# hat2.net
KiCad netlist of a schematic drawn in EAGLE
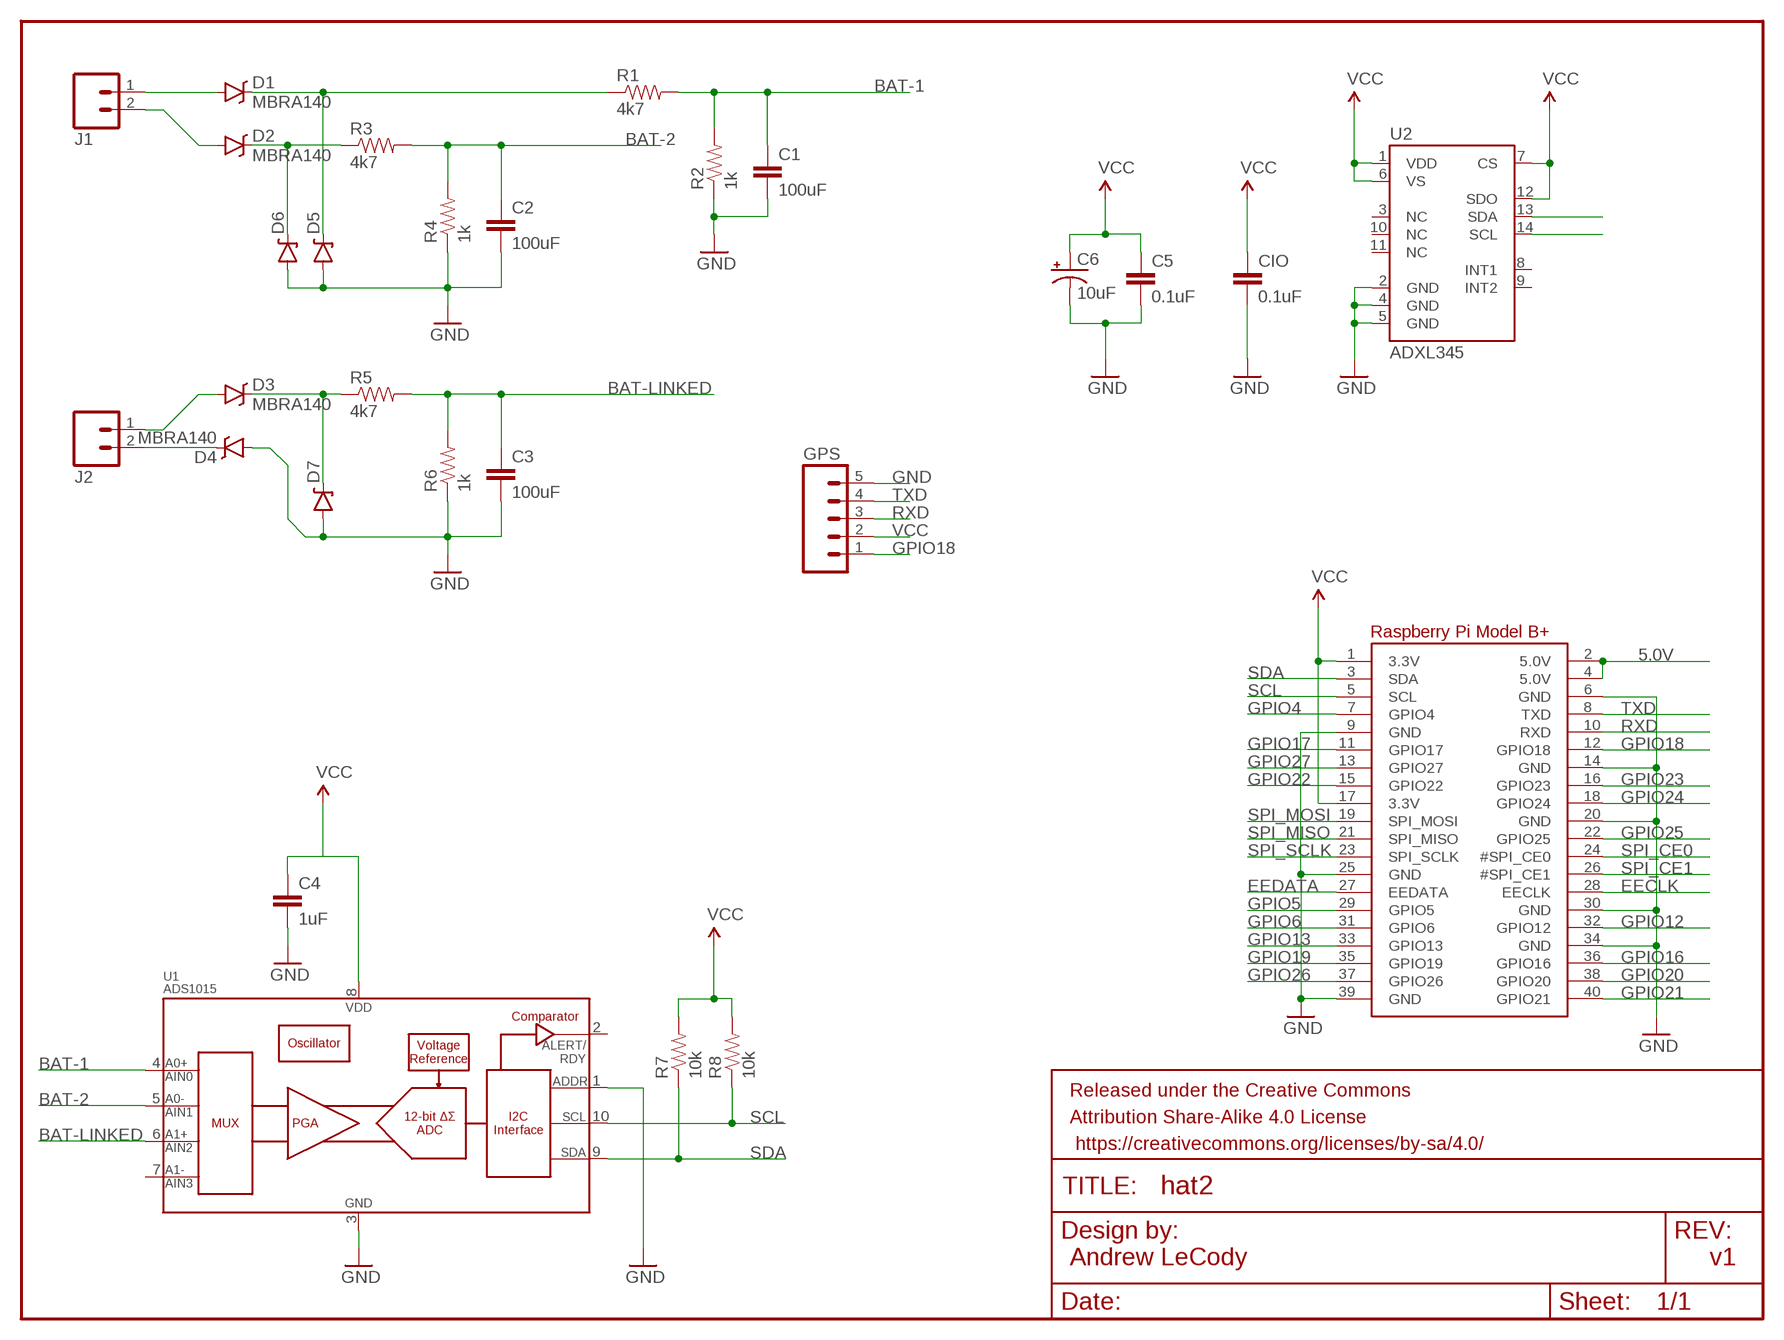
[diagram p0: schematic, sheet 1]

(export (version "E")
  (design (tool "Eeschema 10.0.6"))
  (components
    (comp (ref "C1")
      (value "100uF")
      (footprint "eagle-import:0603-CAP")
      (libsource (lib "eagle-import") (part "SparkFun-Passives_CAP0603-CAP"))
    )
    (comp (ref "C2")
      (value "100uF")
      (footprint "eagle-import:0603-CAP")
      (libsource (lib "eagle-import") (part "SparkFun-Passives_CAP0603-CAP"))
    )
    (comp (ref "C3")
      (value "100uF")
      (footprint "eagle-import:0603-CAP")
      (libsource (lib "eagle-import") (part "SparkFun-Passives_CAP0603-CAP"))
    )
    (comp (ref "C4")
      (value "1uF")
      (footprint "eagle-import:0603-CAP")
      (libsource (lib "eagle-import") (part "SparkFun-Passives_CAP0603-CAP"))
    )
    (comp (ref "C5")
      (value "0.1uF")
      (footprint "eagle-import:0603-CAP")
      (libsource (lib "eagle-import") (part "CAP0603-CAP"))
    )
    (comp (ref "C6")
      (value "10uF")
      (footprint "eagle-import:EIA3216")
      (libsource (lib "eagle-import") (part "CAP_POL1206"))
    )
    (comp (ref "CIO")
      (value "0.1uF")
      (footprint "eagle-import:0603-CAP")
      (libsource (lib "eagle-import") (part "CAP0603-CAP"))
    )
    (comp (ref "D1")
      (value "MBRA140")
      (footprint "eagle-import:SMA-DIODE")
      (libsource (lib "eagle-import") (part "DIODE-SCHOTTKY-MBRA140"))
    )
    (comp (ref "D2")
      (value "MBRA140")
      (footprint "eagle-import:SMA-DIODE")
      (libsource (lib "eagle-import") (part "DIODE-SCHOTTKY-MBRA140"))
    )
    (comp (ref "D3")
      (value "MBRA140")
      (footprint "eagle-import:SMA-DIODE")
      (libsource (lib "eagle-import") (part "DIODE-SCHOTTKY-MBRA140"))
    )
    (comp (ref "D4")
      (value "MBRA140")
      (footprint "eagle-import:SMA-DIODE")
      (libsource (lib "eagle-import") (part "DIODE-SCHOTTKY-MBRA140"))
    )
    (comp (ref "D5")
      (value "DIODE-ZENERSMB")
      (footprint "eagle-import:SMB-DIODE")
      (libsource (lib "eagle-import") (part "DIODE-ZENERSMB"))
    )
    (comp (ref "D6")
      (value "DIODE-ZENERSMB")
      (footprint "eagle-import:SMB-DIODE")
      (libsource (lib "eagle-import") (part "DIODE-ZENERSMB"))
    )
    (comp (ref "D7")
      (value "DIODE-ZENERSMB")
      (footprint "eagle-import:SMB-DIODE")
      (libsource (lib "eagle-import") (part "DIODE-ZENERSMB"))
    )
    (comp (ref "FRAME1")
      (value "FRAME-LETTER")
      (footprint "eagle-import:CREATIVE_COMMONS")
      (libsource (lib "eagle-import") (part "FRAME-LETTER"))
    )
    (comp (ref "GPS")
      (value "M05PTH")
      (footprint "eagle-import:1X05")
      (libsource (lib "eagle-import") (part "M05PTH"))
    )
    (comp (ref "J1")
      (value "M025MM")
      (footprint "eagle-import:SCREWTERMINAL-5MM-2")
      (libsource (lib "eagle-import") (part "M025MM"))
    )
    (comp (ref "J2")
      (value "M025MM")
      (footprint "eagle-import:SCREWTERMINAL-5MM-2")
      (libsource (lib "eagle-import") (part "M025MM"))
    )
    (comp (ref "R1")
      (value "4k7")
      (footprint "eagle-import:0603-RES")
      (libsource (lib "eagle-import") (part "RESISTOR0603-RES"))
    )
    (comp (ref "R2")
      (value "1k")
      (footprint "eagle-import:0603-RES")
      (libsource (lib "eagle-import") (part "RESISTOR0603-RES"))
    )
    (comp (ref "R3")
      (value "4k7")
      (footprint "eagle-import:0603-RES")
      (libsource (lib "eagle-import") (part "RESISTOR0603-RES"))
    )
    (comp (ref "R4")
      (value "1k")
      (footprint "eagle-import:0603-RES")
      (libsource (lib "eagle-import") (part "RESISTOR0603-RES"))
    )
    (comp (ref "R5")
      (value "4k7")
      (footprint "eagle-import:0603-RES")
      (libsource (lib "eagle-import") (part "RESISTOR0603-RES"))
    )
    (comp (ref "R6")
      (value "1k")
      (footprint "eagle-import:0603-RES")
      (libsource (lib "eagle-import") (part "RESISTOR0603-RES"))
    )
    (comp (ref "R7")
      (value "10k")
      (footprint "eagle-import:0603-RES")
      (libsource (lib "eagle-import") (part "RESISTOR0603-RES"))
    )
    (comp (ref "R8")
      (value "10k")
      (footprint "eagle-import:0603-RES")
      (libsource (lib "eagle-import") (part "RESISTOR0603-RES"))
    )
    (comp (ref "RPI1")
      (value "RASPBERRYPI_BPLUS_HATNOSLOTS")
      (footprint "eagle-import:PI_HAT_NOSLOTS")
      (libsource (lib "eagle-import") (part "RASPBERRYPI_BPLUS_HATNOSLOTS"))
    )
    (comp (ref "U1")
      (value "ADS1015")
      (footprint "eagle-import:MSOP10")
      (libsource (lib "eagle-import") (part "ADS1015"))
    )
    (comp (ref "U2")
      (value "ADXL345")
      (footprint "eagle-import:LGA14")
      (libsource (lib "eagle-import") (part "ADXL345"))
    )
  )
  (nets
    (net (code "1") (name "/5.0V") (class "Default")
      (node (ref "RPI1") (pin "2") (pinfunction "5.0V_2") (pintype "power_in"))
      (node (ref "RPI1") (pin "4") (pinfunction "5.0V_4") (pintype "power_in"))
    )
    (net (code "2") (name "/BAT-1") (class "Default")
      (node (ref "C1") (pin "1") (pinfunction "1_1") (pintype "passive"))
      (node (ref "R1") (pin "2") (pinfunction "2_2") (pintype "passive"))
      (node (ref "R2") (pin "2") (pinfunction "2_2") (pintype "passive"))
      (node (ref "U1") (pin "4") (pinfunction "AIN0_4") (pintype "bidirectional"))
    )
    (net (code "3") (name "/BAT-2") (class "Default")
      (node (ref "C2") (pin "1") (pinfunction "1_1") (pintype "passive"))
      (node (ref "R3") (pin "2") (pinfunction "2_2") (pintype "passive"))
      (node (ref "R4") (pin "2") (pinfunction "2_2") (pintype "passive"))
      (node (ref "U1") (pin "5") (pinfunction "AIN1_5") (pintype "bidirectional"))
    )
    (net (code "4") (name "/BAT-LINKED") (class "Default")
      (node (ref "C3") (pin "1") (pinfunction "1_1") (pintype "passive"))
      (node (ref "R5") (pin "2") (pinfunction "2_2") (pintype "passive"))
      (node (ref "R6") (pin "2") (pinfunction "2_2") (pintype "passive"))
      (node (ref "U1") (pin "6") (pinfunction "AIN2_6") (pintype "bidirectional"))
    )
    (net (code "5") (name "/EECLK") (class "Default")
      (node (ref "RPI1") (pin "28") (pinfunction "EECLK_28") (pintype "power_in"))
    )
    (net (code "6") (name "/EEDATA") (class "Default")
      (node (ref "RPI1") (pin "27") (pinfunction "EEDATA_27") (pintype "bidirectional"))
    )
    (net (code "7") (name "/GPIO4") (class "Default")
      (node (ref "RPI1") (pin "7") (pinfunction "GPIO4_7") (pintype "bidirectional"))
    )
    (net (code "8") (name "/GPIO5") (class "Default")
      (node (ref "RPI1") (pin "29") (pinfunction "GPIO5_29") (pintype "bidirectional"))
    )
    (net (code "9") (name "/GPIO6") (class "Default")
      (node (ref "RPI1") (pin "31") (pinfunction "GPIO6_31") (pintype "power_in"))
    )
    (net (code "10") (name "/GPIO12") (class "Default")
      (node (ref "RPI1") (pin "32") (pinfunction "GPIO12_32") (pintype "bidirectional"))
    )
    (net (code "11") (name "/GPIO13") (class "Default")
      (node (ref "RPI1") (pin "33") (pinfunction "GPIO13_33") (pintype "bidirectional"))
    )
    (net (code "12") (name "/GPIO16") (class "Default")
      (node (ref "RPI1") (pin "36") (pinfunction "GPIO16_36") (pintype "power_in"))
    )
    (net (code "13") (name "/GPIO17") (class "Default")
      (node (ref "RPI1") (pin "11") (pinfunction "GPIO17_11") (pintype "bidirectional"))
    )
    (net (code "14") (name "/GPIO18") (class "Default")
      (node (ref "GPS") (pin "1") (pinfunction "1_1") (pintype "passive"))
      (node (ref "RPI1") (pin "12") (pinfunction "GPIO18_12") (pintype "bidirectional"))
    )
    (net (code "15") (name "/GPIO19") (class "Default")
      (node (ref "RPI1") (pin "35") (pinfunction "GPIO19_35") (pintype "bidirectional"))
    )
    (net (code "16") (name "/GPIO20") (class "Default")
      (node (ref "RPI1") (pin "38") (pinfunction "GPIO20_38") (pintype "bidirectional"))
    )
    (net (code "17") (name "/GPIO21") (class "Default")
      (node (ref "RPI1") (pin "40") (pinfunction "GPIO21_40") (pintype "bidirectional"))
    )
    (net (code "18") (name "/GPIO22") (class "Default")
      (node (ref "RPI1") (pin "15") (pinfunction "GPIO22_15") (pintype "bidirectional"))
    )
    (net (code "19") (name "/GPIO23") (class "Default")
      (node (ref "RPI1") (pin "16") (pinfunction "GPIO23_16") (pintype "bidirectional"))
    )
    (net (code "20") (name "/GPIO24") (class "Default")
      (node (ref "RPI1") (pin "18") (pinfunction "GPIO24_18") (pintype "bidirectional"))
    )
    (net (code "21") (name "/GPIO25") (class "Default")
      (node (ref "RPI1") (pin "22") (pinfunction "GPIO25_22") (pintype "bidirectional"))
    )
    (net (code "22") (name "/GPIO26") (class "Default")
      (node (ref "RPI1") (pin "37") (pinfunction "GPIO26_37") (pintype "bidirectional"))
    )
    (net (code "23") (name "/GPIO27") (class "Default")
      (node (ref "RPI1") (pin "13") (pinfunction "GPIO27_13") (pintype "bidirectional"))
    )
    (net (code "24") (name "/RXD") (class "Default")
      (node (ref "GPS") (pin "3") (pinfunction "3_3") (pintype "passive"))
      (node (ref "RPI1") (pin "10") (pinfunction "RXD_10") (pintype "bidirectional"))
    )
    (net (code "25") (name "/SCL") (class "Default")
      (node (ref "R8") (pin "1") (pinfunction "1_1") (pintype "passive"))
      (node (ref "RPI1") (pin "5") (pinfunction "SCL_5") (pintype "bidirectional"))
      (node (ref "U1") (pin "10") (pinfunction "SCL_10") (pintype "bidirectional"))
      (node (ref "U2") (pin "14") (pinfunction "SCL_14") (pintype "bidirectional"))
    )
    (net (code "26") (name "/SDA") (class "Default")
      (node (ref "R7") (pin "1") (pinfunction "1_1") (pintype "passive"))
      (node (ref "RPI1") (pin "3") (pinfunction "SDA_3") (pintype "bidirectional"))
      (node (ref "U1") (pin "9") (pinfunction "SDA_9") (pintype "bidirectional"))
      (node (ref "U2") (pin "13") (pinfunction "SDA_13") (pintype "bidirectional"))
    )
    (net (code "27") (name "/SPI_CE0") (class "Default")
      (node (ref "RPI1") (pin "24") (pinfunction "#SPI_CE0_24") (pintype "bidirectional"))
    )
    (net (code "28") (name "/SPI_CE1") (class "Default")
      (node (ref "RPI1") (pin "26") (pinfunction "#SPI_CE1_26") (pintype "bidirectional"))
    )
    (net (code "29") (name "/SPI_MISO") (class "Default")
      (node (ref "RPI1") (pin "21") (pinfunction "SPI_MISO_21") (pintype "bidirectional"))
    )
    (net (code "30") (name "/SPI_MOSI") (class "Default")
      (node (ref "RPI1") (pin "19") (pinfunction "SPI_MOSI_19") (pintype "bidirectional"))
    )
    (net (code "31") (name "/SPI_SCLK") (class "Default")
      (node (ref "RPI1") (pin "23") (pinfunction "SPI_SCLK_23") (pintype "bidirectional"))
    )
    (net (code "32") (name "/TXD") (class "Default")
      (node (ref "GPS") (pin "4") (pinfunction "4_4") (pintype "passive"))
      (node (ref "RPI1") (pin "8") (pinfunction "TXD_8") (pintype "output"))
    )
    (net (code "33") (name "GND") (class "Default")
      (node (ref "C1") (pin "2") (pinfunction "2_2") (pintype "passive"))
      (node (ref "C2") (pin "2") (pinfunction "2_2") (pintype "passive"))
      (node (ref "C3") (pin "2") (pinfunction "2_2") (pintype "passive"))
      (node (ref "C4") (pin "2") (pinfunction "2_2") (pintype "passive"))
      (node (ref "C5") (pin "2") (pinfunction "2_2") (pintype "passive"))
      (node (ref "C6") (pin "C") (pinfunction "-_C") (pintype "passive"))
      (node (ref "CIO") (pin "2") (pinfunction "2_2") (pintype "passive"))
      (node (ref "D4") (pin "A") (pinfunction "A_A") (pintype "passive"))
      (node (ref "D5") (pin "A") (pinfunction "A_A") (pintype "passive"))
      (node (ref "D6") (pin "A") (pinfunction "A_A") (pintype "passive"))
      (node (ref "D7") (pin "A") (pinfunction "A_A") (pintype "passive"))
      (node (ref "GPS") (pin "5") (pinfunction "5_5") (pintype "passive"))
      (node (ref "R2") (pin "1") (pinfunction "1_1") (pintype "passive"))
      (node (ref "R4") (pin "1") (pinfunction "1_1") (pintype "passive"))
      (node (ref "R6") (pin "1") (pinfunction "1_1") (pintype "passive"))
      (node (ref "RPI1") (pin "14") (pinfunction "GND_14") (pintype "power_in"))
      (node (ref "RPI1") (pin "20") (pinfunction "GND_20") (pintype "power_in"))
      (node (ref "RPI1") (pin "25") (pinfunction "GND_25") (pintype "power_in"))
      (node (ref "RPI1") (pin "30") (pinfunction "GND_30") (pintype "bidirectional"))
      (node (ref "RPI1") (pin "34") (pinfunction "GND_34") (pintype "bidirectional"))
      (node (ref "RPI1") (pin "39") (pinfunction "GND_39") (pintype "power_in"))
      (node (ref "RPI1") (pin "6") (pinfunction "GND_6") (pintype "power_in"))
      (node (ref "RPI1") (pin "9") (pinfunction "GND_9") (pintype "power_in"))
      (node (ref "U1") (pin "1") (pinfunction "ADDR_1") (pintype "bidirectional"))
      (node (ref "U1") (pin "3") (pinfunction "VSS_3") (pintype "bidirectional"))
      (node (ref "U2") (pin "2") (pinfunction "GND_2") (pintype "bidirectional"))
      (node (ref "U2") (pin "4") (pinfunction "GND_4") (pintype "bidirectional"))
      (node (ref "U2") (pin "5") (pinfunction "GND_5") (pintype "bidirectional"))
    )
    (net (code "34") (name "Net-(D1-PadA)") (class "Default")
      (node (ref "D1") (pin "A") (pinfunction "A_A") (pintype "passive"))
      (node (ref "J1") (pin "1") (pinfunction "1_1") (pintype "passive"))
    )
    (net (code "35") (name "Net-(D1-PadC)") (class "Default")
      (node (ref "D1") (pin "C") (pinfunction "C_C") (pintype "passive"))
      (node (ref "D5") (pin "C") (pinfunction "C_C") (pintype "passive"))
      (node (ref "R1") (pin "1") (pinfunction "1_1") (pintype "passive"))
    )
    (net (code "36") (name "Net-(D2-PadA)") (class "Default")
      (node (ref "D2") (pin "A") (pinfunction "A_A") (pintype "passive"))
      (node (ref "J1") (pin "2") (pinfunction "2_2") (pintype "passive"))
    )
    (net (code "37") (name "Net-(D2-PadC)") (class "Default")
      (node (ref "D2") (pin "C") (pinfunction "C_C") (pintype "passive"))
      (node (ref "D6") (pin "C") (pinfunction "C_C") (pintype "passive"))
      (node (ref "R3") (pin "1") (pinfunction "1_1") (pintype "passive"))
    )
    (net (code "38") (name "Net-(D3-PadA)") (class "Default")
      (node (ref "D3") (pin "A") (pinfunction "A_A") (pintype "passive"))
      (node (ref "J2") (pin "1") (pinfunction "1_1") (pintype "passive"))
    )
    (net (code "39") (name "Net-(D3-PadC)") (class "Default")
      (node (ref "D3") (pin "C") (pinfunction "C_C") (pintype "passive"))
      (node (ref "D7") (pin "C") (pinfunction "C_C") (pintype "passive"))
      (node (ref "R5") (pin "1") (pinfunction "1_1") (pintype "passive"))
    )
    (net (code "40") (name "Net-(D4-PadC)") (class "Default")
      (node (ref "D4") (pin "C") (pinfunction "C_C") (pintype "passive"))
      (node (ref "J2") (pin "2") (pinfunction "2_2") (pintype "passive"))
    )
    (net (code "41") (name "VCC") (class "Default")
      (node (ref "C4") (pin "1") (pinfunction "1_1") (pintype "passive"))
      (node (ref "C5") (pin "1") (pinfunction "1_1") (pintype "passive"))
      (node (ref "C6") (pin "A") (pinfunction "+_A") (pintype "passive"))
      (node (ref "CIO") (pin "1") (pinfunction "1_1") (pintype "passive"))
      (node (ref "GPS") (pin "2") (pinfunction "2_2") (pintype "passive"))
      (node (ref "R7") (pin "2") (pinfunction "2_2") (pintype "passive"))
      (node (ref "R8") (pin "2") (pinfunction "2_2") (pintype "passive"))
      (node (ref "RPI1") (pin "1") (pinfunction "3.3V_1") (pintype "power_in"))
      (node (ref "RPI1") (pin "17") (pinfunction "3.3V_17") (pintype "power_in"))
      (node (ref "U1") (pin "8") (pinfunction "VDD_8") (pintype "bidirectional"))
      (node (ref "U2") (pin "1") (pinfunction "VDD_1") (pintype "bidirectional"))
      (node (ref "U2") (pin "12") (pinfunction "SDO_12") (pintype "bidirectional"))
      (node (ref "U2") (pin "6") (pinfunction "VS_6") (pintype "bidirectional"))
      (node (ref "U2") (pin "7") (pinfunction "CS_7") (pintype "bidirectional"))
    )
    (net (code "42") (name "unconnected-(U1-AIN3-Pad7)") (class "Default")
      (node (ref "U1") (pin "7") (pinfunction "AIN3_7") (pintype "bidirectional"))
    )
    (net (code "43") (name "unconnected-(U1-ALERT{slash}RDY-Pad2)") (class "Default")
      (node (ref "U1") (pin "2") (pinfunction "ALERT/RDY_2") (pintype "bidirectional"))
    )
    (net (code "44") (name "unconnected-(U2-INT1-Pad8)") (class "Default")
      (node (ref "U2") (pin "8") (pinfunction "INT1_8") (pintype "bidirectional"))
    )
    (net (code "45") (name "unconnected-(U2-INT2-Pad9)") (class "Default")
      (node (ref "U2") (pin "9") (pinfunction "INT2_9") (pintype "bidirectional"))
    )
    (net (code "46") (name "unconnected-(U2-NC-Pad3)") (class "Default")
      (node (ref "U2") (pin "3") (pinfunction "NC_3") (pintype "bidirectional"))
    )
    (net (code "47") (name "unconnected-(U2-NC-Pad10)") (class "Default")
      (node (ref "U2") (pin "10") (pinfunction "NC_10") (pintype "bidirectional"))
    )
    (net (code "48") (name "unconnected-(U2-NC-Pad11)") (class "Default")
      (node (ref "U2") (pin "11") (pinfunction "NC_11") (pintype "bidirectional"))
    )
  )
)
